# 01-MAIN.net
KiCad netlist of a schematic drawn in Altium Designer
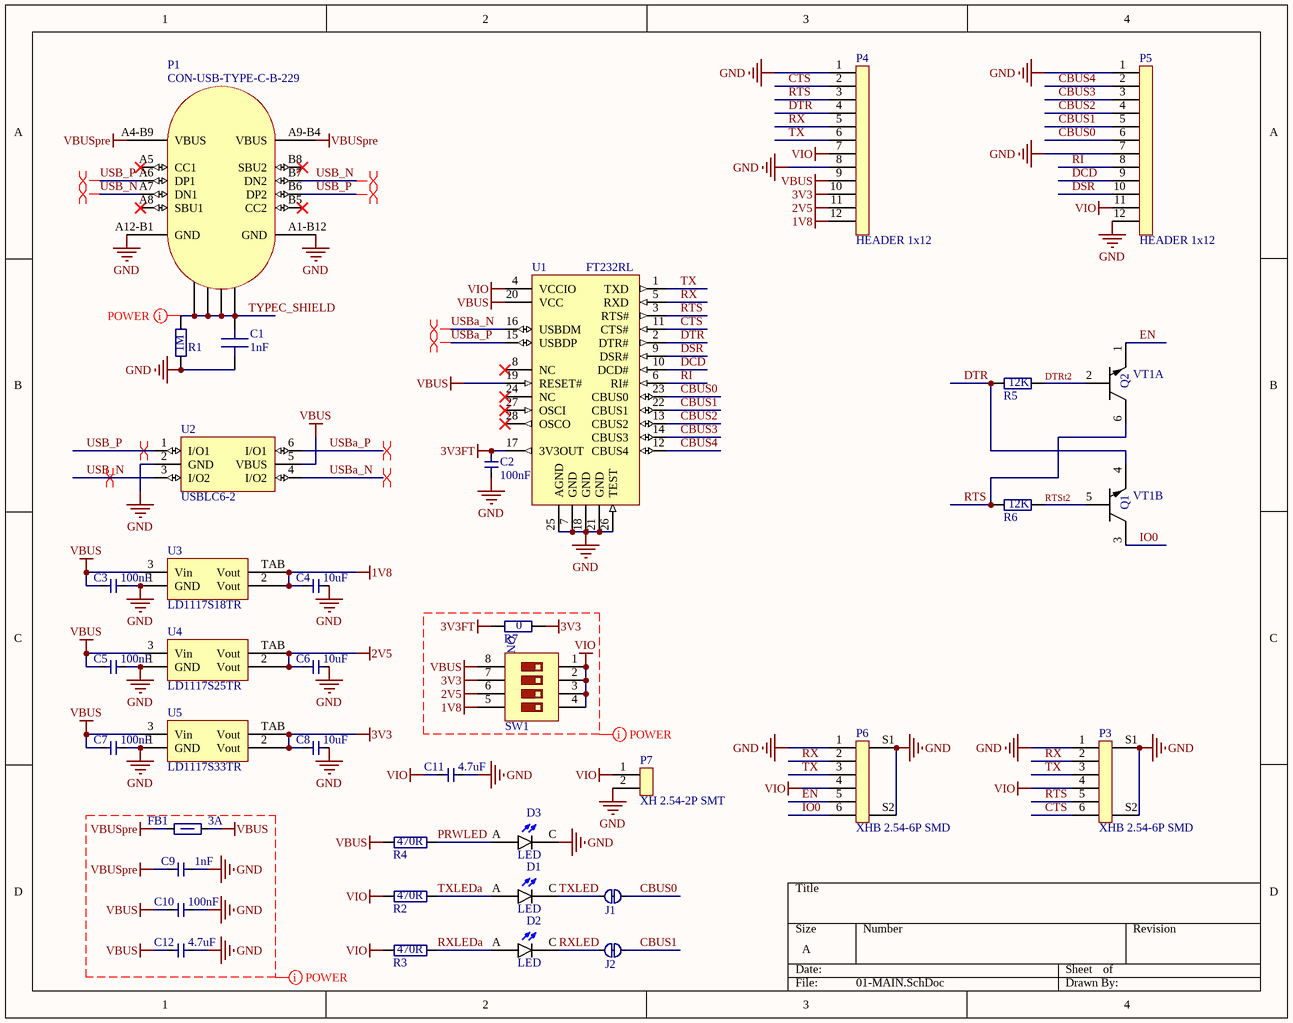
[diagram p0: 01-MAIN.SchDoc]

(export (version "E")
  (design (tool "Eeschema 10.0.6"))
  (components
    (comp (ref "C1")
      (value "1nF")
      (footprint "C1206")
      (description "Ceramic capacitor")
      (fields (field (name "VOLTAGE") "2KV"))
      (libsource (lib "A.Shelestov_Capacitors") (part "C1206_1nF_2KV"))
    )
    (comp (ref "C2")
      (value "100nF")
      (footprint "C0603_NOSILK")
      (description "Ceramic capacitor")
      (fields (field (name "VOLTAGE") "16V") (field (name "MF") "YAGEO"))
      (libsource (lib "Shelestov_Capacitors") (part "C0603_100nF_16V"))
    )
    (comp (ref "C3")
      (value "100nF")
      (footprint "C0603_NOSILK")
      (description "Ceramic capacitor")
      (fields (field (name "VOLTAGE") "16V") (field (name "MF") "YAGEO"))
      (libsource (lib "Shelestov_Capacitors") (part "C0603_100nF_16V"))
    )
    (comp (ref "C4")
      (value "10uF")
      (footprint "C0805")
      (description "Ceramic capacitor")
      (fields (field (name "VOLTAGE") "10V"))
      (libsource (lib "Shelestov_Capacitors") (part "C0805_10uF_10V"))
    )
    (comp (ref "C5")
      (value "100nF")
      (footprint "C0603_NOSILK")
      (description "Ceramic capacitor")
      (fields (field (name "VOLTAGE") "16V") (field (name "MF") "YAGEO"))
      (libsource (lib "Shelestov_Capacitors") (part "C0603_100nF_16V"))
    )
    (comp (ref "C6")
      (value "10uF")
      (footprint "C0805")
      (description "Ceramic capacitor")
      (fields (field (name "VOLTAGE") "10V"))
      (libsource (lib "Shelestov_Capacitors") (part "C0805_10uF_10V"))
    )
    (comp (ref "C7")
      (value "100nF")
      (footprint "C0603_NOSILK")
      (description "Ceramic capacitor")
      (fields (field (name "VOLTAGE") "16V") (field (name "MF") "YAGEO"))
      (libsource (lib "Shelestov_Capacitors") (part "C0603_100nF_16V"))
    )
    (comp (ref "C8")
      (value "10uF")
      (footprint "C0805")
      (description "Ceramic capacitor")
      (fields (field (name "VOLTAGE") "10V"))
      (libsource (lib "Shelestov_Capacitors") (part "C0805_10uF_10V"))
    )
    (comp (ref "C9")
      (value "1nF")
      (footprint "C0603_NOSILK")
      (description "Ceramic capacitor")
      (fields (field (name "VOLTAGE") "25V"))
      (libsource (lib "Shelestov_Capacitors") (part "C0603_1nF_25V"))
    )
    (comp (ref "C10")
      (value "100nF")
      (footprint "C0603_NOSILK")
      (description "Ceramic capacitor")
      (fields (field (name "VOLTAGE") "16V") (field (name "MF") "YAGEO"))
      (libsource (lib "Shelestov_Capacitors") (part "C0603_100nF_16V"))
    )
    (comp (ref "C11")
      (value "4.7uF")
      (footprint "C0805")
      (description "Ceramic capacitor")
      (fields (field (name "VOLTAGE") "10V"))
      (libsource (lib "Shelestov_Capacitors") (part "C0805_4.7uF_10V"))
    )
    (comp (ref "C12")
      (value "4.7uF")
      (footprint "C0805")
      (description "Ceramic capacitor")
      (fields (field (name "VOLTAGE") "10V"))
      (libsource (lib "Shelestov_Capacitors") (part "C0805_4.7uF_10V"))
    )
    (comp (ref "D1")
      (value "LED")
      (footprint "LED_0805")
      (description "Led General")
      (fields (field (name "MF") "Dialight") (field (name "MP") "598-8140-107F"))
      (libsource (lib "Shelestov_Misc") (part "LED"))
    )
    (comp (ref "D2")
      (value "LED")
      (footprint "LED_0805")
      (description "Led General")
      (fields (field (name "MF") "Dialight") (field (name "MP") "598-8140-107F"))
      (libsource (lib "Shelestov_Misc") (part "LED"))
    )
    (comp (ref "D3")
      (value "LED")
      (footprint "LED_0805")
      (description "Led General")
      (fields (field (name "MF") "Dialight") (field (name "MP") "598-8140-107F"))
      (libsource (lib "Shelestov_Misc") (part "LED"))
    )
    (comp (ref "FB1")
      (value "FB_BLM31PG500SN1L")
      (footprint "FER1206")
      (fields (field (name "IMAX") "3A"))
      (libsource (lib "Shelestov_Inductors") (part "FB_BLM31PG500SN1L"))
    )
    (comp (ref "J1")
      (value "CFG2_CUT")
      (footprint "CFG_J_d1_CUT")
      (libsource (lib "Shelestov_Misc") (part "CFG2_CUT"))
    )
    (comp (ref "J2")
      (value "CFG2_CUT")
      (footprint "CFG_J_d1_CUT")
      (libsource (lib "Shelestov_Misc") (part "CFG2_CUT"))
    )
    (comp (ref "P1")
      (value "CON-USB-TYPE-C-B-229")
      (footprint "USB-Type-C-B-229")
      (description "Type C 3A Throughthole Shell, USB2 + PD SMD pins")
      (libsource (lib "ComponentsLib") (part "CON-USB-TYPE-C-B-229"))
    )
    (comp (ref "P3")
      (value "XHB 2.54-6P SMD")
      (footprint "XHB-2.54-6P")
      (description "JST XHB 2.54 pin header SMD Horizontal")
      (libsource (lib "Shelestov_Connectors") (part "XHB 2.54-6P SMD"))
    )
    (comp (ref "P4")
      (value "HEADER 1x12")
      (footprint "HEADER 1x12 2.54 NO PINS")
      (libsource (lib "Shelestov_Connectors") (part "HEADER 1x12"))
    )
    (comp (ref "P5")
      (value "HEADER 1x12")
      (footprint "HEADER 1x12 2.54 NO PINS")
      (libsource (lib "Shelestov_Connectors") (part "HEADER 1x12"))
    )
    (comp (ref "P6")
      (value "XHB 2.54-6P SMD")
      (footprint "XHB-2.54-6P")
      (description "JST XHB 2.54 pin header SMD Horizontal")
      (libsource (lib "Shelestov_Connectors") (part "XHB 2.54-6P SMD"))
    )
    (comp (ref "P7")
      (value "XH 2.54-2P SMT")
      (footprint "XH2.54-2P")
      (description "JST XH 2.54 pin header SMT Vertical")
      (libsource (lib "Shelestov_Connectors") (part "XH 2.54-2P SMT"))
    )
    (comp (ref "R1")
      (value "~")
      (footprint "R2512")
      (description "Resistor General")
      (fields (field (name "TOLERANCE") "5%") (field (name "RESISTANCE") "1M"))
      (libsource (lib "A.Shelestov_Resistors") (part "R2512_1M_5%"))
    )
    (comp (ref "R2")
      (value "~")
      (footprint "R0603_NOSILK")
      (description "Resistor General")
      (fields (field (name "TOLERANCE") "5%") (field (name "RESISTANCE") "470R"))
      (libsource (lib "Shelestov_Resistors") (part "R0603_470R"))
    )
    (comp (ref "R3")
      (value "~")
      (footprint "R0603_NOSILK")
      (description "Resistor General")
      (fields (field (name "TOLERANCE") "5%") (field (name "RESISTANCE") "470R"))
      (libsource (lib "Shelestov_Resistors") (part "R0603_470R"))
    )
    (comp (ref "R4")
      (value "~")
      (footprint "R0603_NOSILK")
      (description "Resistor General")
      (fields (field (name "TOLERANCE") "5%") (field (name "RESISTANCE") "470R"))
      (libsource (lib "Shelestov_Resistors") (part "R0603_470R"))
    )
    (comp (ref "R5")
      (value "~")
      (footprint "R0603_NOSILK")
      (description "Resistor General")
      (fields (field (name "TOLERANCE") "5%") (field (name "RESISTANCE") "12K"))
      (libsource (lib "A.Shelestov_Resistors") (part "R0603_12K"))
    )
    (comp (ref "R6")
      (value "~")
      (footprint "R0603_NOSILK")
      (description "Resistor General")
      (fields (field (name "TOLERANCE") "5%") (field (name "RESISTANCE") "12K"))
      (libsource (lib "A.Shelestov_Resistors") (part "R0603_12K"))
    )
    (comp (ref "R7")
      (value "~")
      (footprint "R0603_NOSILK")
      (description "Resistor General")
      (fields (field (name "RESISTANCE") "0"))
      (libsource (lib "Shelestov_Resistors") (part "R0603_0R"))
    )
    (comp (ref "SW1")
      (value "KLS7-KL-04-N-0-0")
      (footprint "KLS7-KL-04-N-0-0")
      (libsource (lib "Shelestov_Switches") (part "KLS7-KL-04-N-0-0"))
    )
    (comp (ref "U1")
      (value "FT232RL")
      (footprint "SSOP28_0.65_7.8")
      (libsource (lib "Shelestov_IC") (part "FT232RL"))
    )
    (comp (ref "U2")
      (value "USBLC6-2")
      (footprint "SOT-23-6L")
      (description "Very low capacitance ESD protection")
      (libsource (lib "Shelestov_IC") (part "USBLC6-2"))
    )
    (comp (ref "U3")
      (value "LD1117S18TR")
      (footprint "SOT-223")
      (description "Low drop fixed and adjustable positive voltage regulators")
      (libsource (lib "Shelestov_IC") (part "LD1117S18TR"))
    )
    (comp (ref "U4")
      (value "LD1117S25TR")
      (footprint "SOT-223")
      (description "Low drop fixed and adjustable positive voltage regulators")
      (libsource (lib "Shelestov_IC") (part "LD1117S25TR"))
    )
    (comp (ref "U5")
      (value "LD1117S33TR")
      (footprint "SOT-223")
      (description "Low drop fixed and adjustable positive voltage regulators")
      (libsource (lib "Shelestov_IC") (part "LD1117S33TR"))
    )
    (comp (ref "VT1")
      (value "BC847BDW1T1G")
      (footprint "SOT363/SOT65P210X110-6N")
      (description "Dual General Purpose Transistors NPN SOT 363")
      (libsource (lib "ComponentsLib") (part "BC847BDW1T1G"))
    )
  )
  (nets
    (net (code "1") (name "/CBUS0") (class "Default")
      (node (ref "J1") (pin "2") (pinfunction "IN_2") (pintype "passive"))
      (node (ref "P5") (pin "6") (pinfunction "6_6") (pintype "passive"))
      (node (ref "U1") (pin "23") (pinfunction "CBUS0_23") (pintype "bidirectional"))
    )
    (net (code "2") (name "/CBUS1") (class "Default")
      (node (ref "J2") (pin "2") (pinfunction "IN_2") (pintype "passive"))
      (node (ref "P5") (pin "5") (pinfunction "5_5") (pintype "passive"))
      (node (ref "U1") (pin "22") (pinfunction "CBUS1_22") (pintype "bidirectional"))
    )
    (net (code "3") (name "/CBUS2") (class "Default")
      (node (ref "P5") (pin "4") (pinfunction "4_4") (pintype "passive"))
      (node (ref "U1") (pin "13") (pinfunction "CBUS2_13") (pintype "bidirectional"))
    )
    (net (code "4") (name "/CBUS3") (class "Default")
      (node (ref "P5") (pin "3") (pinfunction "3_3") (pintype "passive"))
      (node (ref "U1") (pin "14") (pinfunction "CBUS3_14") (pintype "bidirectional"))
    )
    (net (code "5") (name "/CBUS4") (class "Default")
      (node (ref "P5") (pin "2") (pinfunction "2_2") (pintype "passive"))
      (node (ref "U1") (pin "12") (pinfunction "CBUS4_12") (pintype "bidirectional"))
    )
    (net (code "6") (name "/CTS") (class "Default")
      (node (ref "P3") (pin "6") (pinfunction "6_6") (pintype "passive"))
      (node (ref "P4") (pin "2") (pinfunction "2_2") (pintype "passive"))
      (node (ref "U1") (pin "11") (pinfunction "CTS#_11") (pintype "input"))
    )
    (net (code "7") (name "/DCD") (class "Default")
      (node (ref "P5") (pin "9") (pinfunction "9_9") (pintype "passive"))
      (node (ref "U1") (pin "10") (pinfunction "DCD#_10") (pintype "input"))
    )
    (net (code "8") (name "/DSR") (class "Default")
      (node (ref "P5") (pin "10") (pinfunction "10_10") (pintype "passive"))
      (node (ref "U1") (pin "9") (pinfunction "DSR#_9") (pintype "input"))
    )
    (net (code "9") (name "/DTR") (class "Default")
      (node (ref "P4") (pin "4") (pinfunction "4_4") (pintype "passive"))
      (node (ref "R5") (pin "1") (pinfunction "1_1") (pintype "passive"))
      (node (ref "U1") (pin "2") (pinfunction "DTR#_2") (pintype "output"))
      (node (ref "VT1") (pin "4") (pinfunction "4_4") (pintype "passive"))
    )
    (net (code "10") (name "/DTRt2") (class "Default")
      (node (ref "R5") (pin "2") (pinfunction "2_2") (pintype "passive"))
      (node (ref "VT1") (pin "2") (pinfunction "2_2") (pintype "passive"))
    )
    (net (code "11") (name "/EN") (class "Default")
      (node (ref "P6") (pin "5") (pinfunction "5_5") (pintype "passive"))
      (node (ref "VT1") (pin "1") (pinfunction "1_1") (pintype "passive"))
    )
    (net (code "12") (name "/IO0") (class "Default")
      (node (ref "P6") (pin "6") (pinfunction "6_6") (pintype "passive"))
      (node (ref "VT1") (pin "3") (pinfunction "3_3") (pintype "passive"))
    )
    (net (code "13") (name "/PRWLED") (class "Default")
      (node (ref "D3") (pin "A") (pinfunction "A_A") (pintype "passive"))
      (node (ref "R4") (pin "2") (pinfunction "2_2") (pintype "passive"))
    )
    (net (code "14") (name "/RI") (class "Default")
      (node (ref "P5") (pin "8") (pinfunction "8_8") (pintype "passive"))
      (node (ref "U1") (pin "6") (pinfunction "RI#_6") (pintype "input"))
    )
    (net (code "15") (name "/RTS") (class "Default")
      (node (ref "P3") (pin "5") (pinfunction "5_5") (pintype "passive"))
      (node (ref "P4") (pin "3") (pinfunction "3_3") (pintype "passive"))
      (node (ref "R6") (pin "1") (pinfunction "1_1") (pintype "passive"))
      (node (ref "U1") (pin "3") (pinfunction "RTS#_3") (pintype "output"))
      (node (ref "VT1") (pin "6") (pinfunction "6_6") (pintype "passive"))
    )
    (net (code "16") (name "/RTSt2") (class "Default")
      (node (ref "R6") (pin "2") (pinfunction "2_2") (pintype "passive"))
      (node (ref "VT1") (pin "5") (pinfunction "5_5") (pintype "passive"))
    )
    (net (code "17") (name "/RX") (class "Default")
      (node (ref "P3") (pin "2") (pinfunction "2_2") (pintype "passive"))
      (node (ref "P4") (pin "5") (pinfunction "5_5") (pintype "passive"))
      (node (ref "P6") (pin "2") (pinfunction "2_2") (pintype "passive"))
      (node (ref "U1") (pin "5") (pinfunction "RXD_5") (pintype "input"))
    )
    (net (code "18") (name "/RXLED") (class "Default")
      (node (ref "D2") (pin "C") (pinfunction "C_C") (pintype "passive"))
      (node (ref "J2") (pin "1") (pinfunction "A_1") (pintype "passive"))
    )
    (net (code "19") (name "/RXLEDa") (class "Default")
      (node (ref "D2") (pin "A") (pinfunction "A_A") (pintype "passive"))
      (node (ref "R3") (pin "2") (pinfunction "2_2") (pintype "passive"))
    )
    (net (code "20") (name "/TX") (class "Default")
      (node (ref "P3") (pin "3") (pinfunction "3_3") (pintype "passive"))
      (node (ref "P4") (pin "6") (pinfunction "6_6") (pintype "passive"))
      (node (ref "P6") (pin "3") (pinfunction "3_3") (pintype "passive"))
      (node (ref "U1") (pin "1") (pinfunction "TXD_1") (pintype "output"))
    )
    (net (code "21") (name "/TXLED") (class "Default")
      (node (ref "D1") (pin "C") (pinfunction "C_C") (pintype "passive"))
      (node (ref "J1") (pin "1") (pinfunction "A_1") (pintype "passive"))
    )
    (net (code "22") (name "/TXLEDa") (class "Default")
      (node (ref "D1") (pin "A") (pinfunction "A_A") (pintype "passive"))
      (node (ref "R2") (pin "2") (pinfunction "2_2") (pintype "passive"))
    )
    (net (code "23") (name "/TYPEC_SHIELD") (class "Default")
      (node (ref "C1") (pin "2") (pinfunction "2_2") (pintype "passive"))
      (node (ref "P1") (pin "SHIELD") (pinfunction "SHIELD_SHIELD") (pintype "power_in"))
      (node (ref "R1") (pin "2") (pinfunction "2_2") (pintype "passive"))
    )
    (net (code "24") (name "/USB_N") (class "Default")
      (node (ref "P1") (pin "A7") (pinfunction "DN1_A7") (pintype "bidirectional"))
      (node (ref "P1") (pin "B7") (pinfunction "DN2_B7") (pintype "bidirectional"))
      (node (ref "U2") (pin "3") (pinfunction "I/O2_3") (pintype "bidirectional"))
    )
    (net (code "25") (name "/USB_P") (class "Default")
      (node (ref "P1") (pin "A6") (pinfunction "DP1_A6") (pintype "bidirectional"))
      (node (ref "P1") (pin "B6") (pinfunction "DP2_B6") (pintype "bidirectional"))
      (node (ref "U2") (pin "1") (pinfunction "I/O1_1") (pintype "bidirectional"))
    )
    (net (code "26") (name "/USBa_N") (class "Default")
      (node (ref "U1") (pin "16") (pinfunction "USBDM_16") (pintype "bidirectional"))
      (node (ref "U2") (pin "4") (pinfunction "I/O2_4") (pintype "bidirectional"))
    )
    (net (code "27") (name "/USBa_P") (class "Default")
      (node (ref "U1") (pin "15") (pinfunction "USBDP_15") (pintype "bidirectional"))
      (node (ref "U2") (pin "6") (pinfunction "I/O1_6") (pintype "bidirectional"))
    )
    (net (code "28") (name "1V8") (class "Default")
      (node (ref "C4") (pin "1") (pinfunction "1_1") (pintype "passive"))
      (node (ref "P4") (pin "12") (pinfunction "12_12") (pintype "passive"))
      (node (ref "SW1") (pin "5") (pinfunction "5_5") (pintype "passive"))
      (node (ref "U3") (pin "2") (pinfunction "Vout_2") (pintype "passive"))
      (node (ref "U3") (pin "TAB") (pinfunction "Vout_TAB") (pintype "passive"))
    )
    (net (code "29") (name "2V5") (class "Default")
      (node (ref "C6") (pin "1") (pinfunction "1_1") (pintype "passive"))
      (node (ref "P4") (pin "11") (pinfunction "11_11") (pintype "passive"))
      (node (ref "SW1") (pin "6") (pinfunction "6_6") (pintype "passive"))
      (node (ref "U4") (pin "2") (pinfunction "Vout_2") (pintype "passive"))
      (node (ref "U4") (pin "TAB") (pinfunction "Vout_TAB") (pintype "passive"))
    )
    (net (code "30") (name "3V3") (class "Default")
      (node (ref "C8") (pin "1") (pinfunction "1_1") (pintype "passive"))
      (node (ref "P4") (pin "10") (pinfunction "10_10") (pintype "passive"))
      (node (ref "R7") (pin "2") (pinfunction "2_2") (pintype "passive"))
      (node (ref "SW1") (pin "7") (pinfunction "7_7") (pintype "passive"))
      (node (ref "U5") (pin "2") (pinfunction "Vout_2") (pintype "passive"))
      (node (ref "U5") (pin "TAB") (pinfunction "Vout_TAB") (pintype "passive"))
    )
    (net (code "31") (name "3V3FT") (class "Default")
      (node (ref "C2") (pin "2") (pinfunction "2_2") (pintype "passive"))
      (node (ref "R7") (pin "1") (pinfunction "1_1") (pintype "passive"))
      (node (ref "U1") (pin "17") (pinfunction "3V3OUT_17") (pintype "output"))
    )
    (net (code "32") (name "GND") (class "Default")
      (node (ref "C1") (pin "1") (pinfunction "1_1") (pintype "passive"))
      (node (ref "C10") (pin "1") (pinfunction "1_1") (pintype "passive"))
      (node (ref "C11") (pin "1") (pinfunction "1_1") (pintype "passive"))
      (node (ref "C12") (pin "1") (pinfunction "1_1") (pintype "passive"))
      (node (ref "C2") (pin "1") (pinfunction "1_1") (pintype "passive"))
      (node (ref "C3") (pin "1") (pinfunction "1_1") (pintype "passive"))
      (node (ref "C4") (pin "2") (pinfunction "2_2") (pintype "passive"))
      (node (ref "C5") (pin "1") (pinfunction "1_1") (pintype "passive"))
      (node (ref "C6") (pin "2") (pinfunction "2_2") (pintype "passive"))
      (node (ref "C7") (pin "1") (pinfunction "1_1") (pintype "passive"))
      (node (ref "C8") (pin "2") (pinfunction "2_2") (pintype "passive"))
      (node (ref "C9") (pin "2") (pinfunction "2_2") (pintype "passive"))
      (node (ref "D3") (pin "C") (pinfunction "C_C") (pintype "passive"))
      (node (ref "P1") (pin "A1-B12") (pinfunction "GND_A1-B12") (pintype "power_in"))
      (node (ref "P1") (pin "A12-B1") (pinfunction "GND_A12-B1") (pintype "power_in"))
      (node (ref "P3") (pin "1") (pinfunction "1_1") (pintype "passive"))
      (node (ref "P3") (pin "S1") (pinfunction "S1_S1") (pintype "passive"))
      (node (ref "P3") (pin "S2") (pinfunction "S2_S2") (pintype "passive"))
      (node (ref "P4") (pin "1") (pinfunction "1_1") (pintype "passive"))
      (node (ref "P4") (pin "8") (pinfunction "8_8") (pintype "passive"))
      (node (ref "P5") (pin "1") (pinfunction "1_1") (pintype "passive"))
      (node (ref "P5") (pin "12") (pinfunction "12_12") (pintype "passive"))
      (node (ref "P5") (pin "7") (pinfunction "7_7") (pintype "passive"))
      (node (ref "P6") (pin "1") (pinfunction "1_1") (pintype "passive"))
      (node (ref "P6") (pin "S1") (pinfunction "S1_S1") (pintype "passive"))
      (node (ref "P6") (pin "S2") (pinfunction "S2_S2") (pintype "passive"))
      (node (ref "P7") (pin "2") (pinfunction "2_2") (pintype "passive"))
      (node (ref "R1") (pin "1") (pinfunction "1_1") (pintype "passive"))
      (node (ref "U1") (pin "18") (pinfunction "GND_18") (pintype "power_in"))
      (node (ref "U1") (pin "21") (pinfunction "GND_21") (pintype "power_in"))
      (node (ref "U1") (pin "25") (pinfunction "AGND_25") (pintype "power_in"))
      (node (ref "U1") (pin "26") (pinfunction "TEST_26") (pintype "input"))
      (node (ref "U1") (pin "7") (pinfunction "GND_7") (pintype "power_in"))
      (node (ref "U2") (pin "2") (pinfunction "GND_2") (pintype "power_in"))
      (node (ref "U3") (pin "1") (pinfunction "GND_1") (pintype "passive"))
      (node (ref "U4") (pin "1") (pinfunction "GND_1") (pintype "passive"))
      (node (ref "U5") (pin "1") (pinfunction "GND_1") (pintype "passive"))
    )
    (net (code "33") (name "VBUS") (class "Default")
      (node (ref "C10") (pin "2") (pinfunction "2_2") (pintype "passive"))
      (node (ref "C12") (pin "2") (pinfunction "2_2") (pintype "passive"))
      (node (ref "C3") (pin "2") (pinfunction "2_2") (pintype "passive"))
      (node (ref "C5") (pin "2") (pinfunction "2_2") (pintype "passive"))
      (node (ref "C7") (pin "2") (pinfunction "2_2") (pintype "passive"))
      (node (ref "FB1") (pin "2") (pinfunction "2_2") (pintype "passive"))
      (node (ref "P4") (pin "9") (pinfunction "9_9") (pintype "passive"))
      (node (ref "R4") (pin "1") (pinfunction "1_1") (pintype "passive"))
      (node (ref "SW1") (pin "8") (pinfunction "8_8") (pintype "passive"))
      (node (ref "U1") (pin "19") (pinfunction "RESET#_19") (pintype "input"))
      (node (ref "U1") (pin "20") (pinfunction "VCC_20") (pintype "power_in"))
      (node (ref "U2") (pin "5") (pinfunction "VBUS_5") (pintype "power_in"))
      (node (ref "U3") (pin "3") (pinfunction "Vin_3") (pintype "passive"))
      (node (ref "U4") (pin "3") (pinfunction "Vin_3") (pintype "passive"))
      (node (ref "U5") (pin "3") (pinfunction "Vin_3") (pintype "passive"))
    )
    (net (code "34") (name "VBUSpre") (class "Default")
      (node (ref "C9") (pin "1") (pinfunction "1_1") (pintype "passive"))
      (node (ref "FB1") (pin "1") (pinfunction "1_1") (pintype "passive"))
      (node (ref "P1") (pin "A4-B9") (pinfunction "VBUS_A4-B9") (pintype "power_in"))
      (node (ref "P1") (pin "A9-B4") (pinfunction "VBUS_A9-B4") (pintype "power_in"))
    )
    (net (code "35") (name "VIO") (class "Default")
      (node (ref "C11") (pin "2") (pinfunction "2_2") (pintype "passive"))
      (node (ref "P3") (pin "4") (pinfunction "4_4") (pintype "passive"))
      (node (ref "P4") (pin "7") (pinfunction "7_7") (pintype "passive"))
      (node (ref "P5") (pin "11") (pinfunction "11_11") (pintype "passive"))
      (node (ref "P6") (pin "4") (pinfunction "4_4") (pintype "passive"))
      (node (ref "P7") (pin "1") (pinfunction "1_1") (pintype "passive"))
      (node (ref "R2") (pin "1") (pinfunction "1_1") (pintype "passive"))
      (node (ref "R3") (pin "1") (pinfunction "1_1") (pintype "passive"))
      (node (ref "SW1") (pin "1") (pinfunction "1_1") (pintype "passive"))
      (node (ref "SW1") (pin "2") (pinfunction "2_2") (pintype "passive"))
      (node (ref "SW1") (pin "3") (pinfunction "3_3") (pintype "passive"))
      (node (ref "SW1") (pin "4") (pinfunction "4_4") (pintype "passive"))
      (node (ref "U1") (pin "4") (pinfunction "VCCIO_4") (pintype "power_in"))
    )
    (net (code "36") (name "unconnected-(P1-CC1-PadA5)") (class "Default")
      (node (ref "P1") (pin "A5") (pinfunction "CC1_A5") (pintype "bidirectional+no_connect"))
    )
    (net (code "37") (name "unconnected-(P1-CC2-PadB5)") (class "Default")
      (node (ref "P1") (pin "B5") (pinfunction "CC2_B5") (pintype "bidirectional+no_connect"))
    )
    (net (code "38") (name "unconnected-(P1-SBU1-PadA8)") (class "Default")
      (node (ref "P1") (pin "A8") (pinfunction "SBU1_A8") (pintype "bidirectional+no_connect"))
    )
    (net (code "39") (name "unconnected-(P1-SBU2-PadB8)") (class "Default")
      (node (ref "P1") (pin "B8") (pinfunction "SBU2_B8") (pintype "bidirectional+no_connect"))
    )
    (net (code "40") (name "unconnected-(U1-NC-Pad8)") (class "Default")
      (node (ref "U1") (pin "8") (pinfunction "NC_8") (pintype "passive+no_connect"))
    )
    (net (code "41") (name "unconnected-(U1-NC-Pad24)") (class "Default")
      (node (ref "U1") (pin "24") (pinfunction "NC_24") (pintype "passive+no_connect"))
    )
    (net (code "42") (name "unconnected-(U1-OSCI-Pad27)") (class "Default")
      (node (ref "U1") (pin "27") (pinfunction "OSCI_27") (pintype "input+no_connect"))
    )
    (net (code "43") (name "unconnected-(U1-OSCO-Pad28)") (class "Default")
      (node (ref "U1") (pin "28") (pinfunction "OSCO_28") (pintype "output+no_connect"))
    )
  )
)
